# untitled.net
KiCad netlist of a schematic drawn in EAGLE
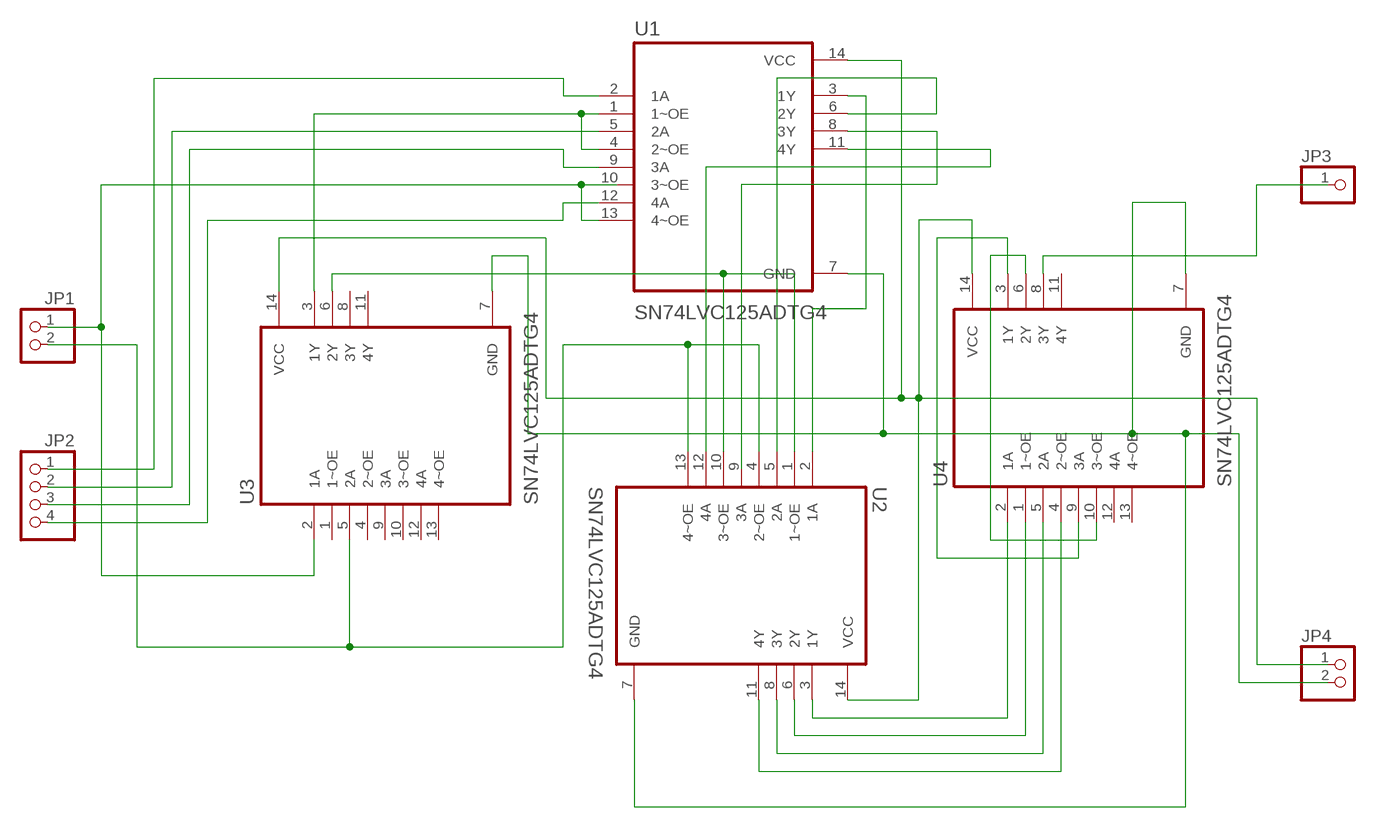
[diagram p0: schematic, sheet 1]

(export (version "E")
  (design (tool "Eeschema 10.0.6"))
  (components
    (comp (ref "JP1")
      (value "PINHD-1X2")
      (footprint "eagle-import:1X02")
      (libsource (lib "eagle-import") (part "PINHD-1X2"))
    )
    (comp (ref "JP2")
      (value "PINHD-1X4")
      (footprint "eagle-import:1X04")
      (libsource (lib "eagle-import") (part "PINHD-1X4"))
    )
    (comp (ref "JP3")
      (value "PINHD-1X1")
      (footprint "eagle-import:1X01")
      (libsource (lib "eagle-import") (part "PINHD-1X1"))
    )
    (comp (ref "JP4")
      (value "PINHD-1X2")
      (footprint "eagle-import:1X02")
      (libsource (lib "eagle-import") (part "PINHD-1X2"))
    )
    (comp (ref "U1")
      (value "SN74LVC125ADTG4")
      (footprint "eagle-import:SOIC127P600X175-14N")
      (fields (field (name "MF") "Texas Instruments"))
      (libsource (lib "eagle-import") (part "SN74LVC125ADTG4"))
    )
    (comp (ref "U2")
      (value "SN74LVC125ADTG4")
      (footprint "eagle-import:SOIC127P600X175-14N")
      (fields (field (name "MF") "Texas Instruments"))
      (libsource (lib "eagle-import") (part "SN74LVC125ADTG4"))
    )
    (comp (ref "U3")
      (value "SN74LVC125ADTG4")
      (footprint "eagle-import:SOIC127P600X175-14N")
      (fields (field (name "MF") "Texas Instruments"))
      (libsource (lib "eagle-import") (part "SN74LVC125ADTG4"))
    )
    (comp (ref "U4")
      (value "SN74LVC125ADTG4")
      (footprint "eagle-import:SOIC127P600X175-14N")
      (fields (field (name "MF") "Texas Instruments"))
      (libsource (lib "eagle-import") (part "SN74LVC125ADTG4"))
    )
  )
  (nets
    (net (code "1") (name "Net-(U1-1A)") (class "Default")
      (node (ref "JP2") (pin "1") (pinfunction "1_1") (pintype "passive"))
      (node (ref "U1") (pin "2") (pinfunction "1A_2") (pintype "input"))
    )
    (net (code "2") (name "Net-(U1-1Y)") (class "Default")
      (node (ref "U1") (pin "3") (pinfunction "1Y_3") (pintype "output"))
      (node (ref "U2") (pin "2") (pinfunction "1A_2") (pintype "input"))
    )
    (net (code "3") (name "Net-(U1-1~{OE})") (class "Default")
      (node (ref "U1") (pin "1") (pinfunction "1~{OE}_1") (pintype "input"))
      (node (ref "U1") (pin "4") (pinfunction "2~{OE}_4") (pintype "input"))
      (node (ref "U3") (pin "3") (pinfunction "1Y_3") (pintype "output"))
    )
    (net (code "4") (name "Net-(U1-2A)") (class "Default")
      (node (ref "JP2") (pin "2") (pinfunction "2_2") (pintype "passive"))
      (node (ref "U1") (pin "5") (pinfunction "2A_5") (pintype "input"))
    )
    (net (code "5") (name "Net-(U1-2Y)") (class "Default")
      (node (ref "U1") (pin "6") (pinfunction "2Y_6") (pintype "output"))
      (node (ref "U2") (pin "5") (pinfunction "2A_5") (pintype "input"))
    )
    (net (code "6") (name "Net-(U1-3A)") (class "Default")
      (node (ref "JP2") (pin "3") (pinfunction "3_3") (pintype "passive"))
      (node (ref "U1") (pin "9") (pinfunction "3A_9") (pintype "input"))
    )
    (net (code "7") (name "Net-(U1-4A)") (class "Default")
      (node (ref "JP2") (pin "4") (pinfunction "4_4") (pintype "passive"))
      (node (ref "U1") (pin "12") (pinfunction "4A_12") (pintype "input"))
    )
    (net (code "8") (name "Net-(U1-4Y)") (class "Default")
      (node (ref "U1") (pin "11") (pinfunction "4Y_11") (pintype "output"))
      (node (ref "U2") (pin "12") (pinfunction "4A_12") (pintype "input"))
    )
    (net (code "9") (name "Net-(U1-4~{OE})") (class "Default")
      (node (ref "JP1") (pin "1") (pinfunction "1_1") (pintype "passive"))
      (node (ref "U1") (pin "13") (pinfunction "4~{OE}_13") (pintype "input"))
      (node (ref "U3") (pin "2") (pinfunction "1A_2") (pintype "input"))
    )
    (net (code "10") (name "Net-(U1-GND)") (class "Default")
      (node (ref "JP4") (pin "2") (pinfunction "2_2") (pintype "passive"))
      (node (ref "U1") (pin "7") (pinfunction "GND_7") (pintype "power_in"))
      (node (ref "U2") (pin "7") (pinfunction "GND_7") (pintype "power_in"))
      (node (ref "U3") (pin "7") (pinfunction "GND_7") (pintype "power_in"))
      (node (ref "U4") (pin "7") (pinfunction "GND_7") (pintype "power_in"))
    )
    (net (code "11") (name "Net-(U1-VCC)") (class "Default")
      (node (ref "JP4") (pin "1") (pinfunction "1_1") (pintype "passive"))
      (node (ref "U1") (pin "14") (pinfunction "VCC_14") (pintype "power_in"))
      (node (ref "U2") (pin "14") (pinfunction "VCC_14") (pintype "power_in"))
      (node (ref "U3") (pin "14") (pinfunction "VCC_14") (pintype "power_in"))
      (node (ref "U4") (pin "14") (pinfunction "VCC_14") (pintype "power_in"))
    )
    (net (code "12") (name "Net-(U2-1Y)") (class "Default")
      (node (ref "U2") (pin "3") (pinfunction "1Y_3") (pintype "output"))
      (node (ref "U4") (pin "2") (pinfunction "1A_2") (pintype "input"))
    )
    (net (code "13") (name "Net-(U2-1~{OE})") (class "Default")
      (node (ref "U2") (pin "1") (pinfunction "1~{OE}_1") (pintype "input"))
      (node (ref "U2") (pin "10") (pinfunction "3~{OE}_10") (pintype "input"))
      (node (ref "U3") (pin "6") (pinfunction "2Y_6") (pintype "output"))
    )
    (net (code "14") (name "Net-(U2-2Y)") (class "Default")
      (node (ref "U2") (pin "6") (pinfunction "2Y_6") (pintype "output"))
      (node (ref "U4") (pin "1") (pinfunction "1~{OE}_1") (pintype "input"))
    )
    (net (code "15") (name "Net-(U2-2~{OE})") (class "Default")
      (node (ref "JP1") (pin "2") (pinfunction "2_2") (pintype "passive"))
      (node (ref "U2") (pin "13") (pinfunction "4~{OE}_13") (pintype "input"))
      (node (ref "U2") (pin "4") (pinfunction "2~{OE}_4") (pintype "input"))
      (node (ref "U3") (pin "5") (pinfunction "2A_5") (pintype "input"))
    )
    (net (code "16") (name "Net-(U2-3Y)") (class "Default")
      (node (ref "U2") (pin "8") (pinfunction "3Y_8") (pintype "output"))
      (node (ref "U4") (pin "5") (pinfunction "2A_5") (pintype "input"))
    )
    (net (code "17") (name "Net-(U2-4Y)") (class "Default")
      (node (ref "U2") (pin "11") (pinfunction "4Y_11") (pintype "output"))
      (node (ref "U4") (pin "4") (pinfunction "2~{OE}_4") (pintype "input"))
    )
    (net (code "18") (name "Net-(U4-1Y)") (class "Default")
      (node (ref "U4") (pin "3") (pinfunction "1Y_3") (pintype "output"))
      (node (ref "U4") (pin "9") (pinfunction "3A_9") (pintype "input"))
    )
    (net (code "19") (name "Net-(U4-2Y)") (class "Default")
      (node (ref "U4") (pin "10") (pinfunction "3~{OE}_10") (pintype "input"))
      (node (ref "U4") (pin "6") (pinfunction "2Y_6") (pintype "output"))
    )
    (net (code "20") (name "Net-(U4-3Y)") (class "Default")
      (node (ref "JP3") (pin "1") (pinfunction "1_1") (pintype "passive"))
      (node (ref "U4") (pin "8") (pinfunction "3Y_8") (pintype "output"))
    )
    (net (code "21") (name "unconnected-(U1-3Y-Pad8)") (class "Default")
      (node (ref "U1") (pin "8") (pinfunction "3Y_8") (pintype "output"))
    )
    (net (code "22") (name "unconnected-(U1-3~{OE}-Pad10)") (class "Default")
      (node (ref "U1") (pin "10") (pinfunction "3~{OE}_10") (pintype "input"))
    )
    (net (code "23") (name "unconnected-(U2-3A-Pad9)") (class "Default")
      (node (ref "U2") (pin "9") (pinfunction "3A_9") (pintype "input"))
    )
    (net (code "24") (name "unconnected-(U3-1~{OE}-Pad1)") (class "Default")
      (node (ref "U3") (pin "1") (pinfunction "1~{OE}_1") (pintype "input"))
    )
    (net (code "25") (name "unconnected-(U3-2~{OE}-Pad4)") (class "Default")
      (node (ref "U3") (pin "4") (pinfunction "2~{OE}_4") (pintype "input"))
    )
    (net (code "26") (name "unconnected-(U3-3A-Pad9)") (class "Default")
      (node (ref "U3") (pin "9") (pinfunction "3A_9") (pintype "input"))
    )
    (net (code "27") (name "unconnected-(U3-3Y-Pad8)") (class "Default")
      (node (ref "U3") (pin "8") (pinfunction "3Y_8") (pintype "output"))
    )
    (net (code "28") (name "unconnected-(U3-3~{OE}-Pad10)") (class "Default")
      (node (ref "U3") (pin "10") (pinfunction "3~{OE}_10") (pintype "input"))
    )
    (net (code "29") (name "unconnected-(U3-4A-Pad12)") (class "Default")
      (node (ref "U3") (pin "12") (pinfunction "4A_12") (pintype "input"))
    )
    (net (code "30") (name "unconnected-(U3-4Y-Pad11)") (class "Default")
      (node (ref "U3") (pin "11") (pinfunction "4Y_11") (pintype "output"))
    )
    (net (code "31") (name "unconnected-(U3-4~{OE}-Pad13)") (class "Default")
      (node (ref "U3") (pin "13") (pinfunction "4~{OE}_13") (pintype "input"))
    )
    (net (code "32") (name "unconnected-(U4-4A-Pad12)") (class "Default")
      (node (ref "U4") (pin "12") (pinfunction "4A_12") (pintype "input"))
    )
    (net (code "33") (name "unconnected-(U4-4Y-Pad11)") (class "Default")
      (node (ref "U4") (pin "11") (pinfunction "4Y_11") (pintype "output"))
    )
    (net (code "34") (name "unconnected-(U4-4~{OE}-Pad13)") (class "Default")
      (node (ref "U4") (pin "13") (pinfunction "4~{OE}_13") (pintype "input"))
    )
  )
)
